# ICS.net
KiCad netlist of a schematic drawn in Altium Designer
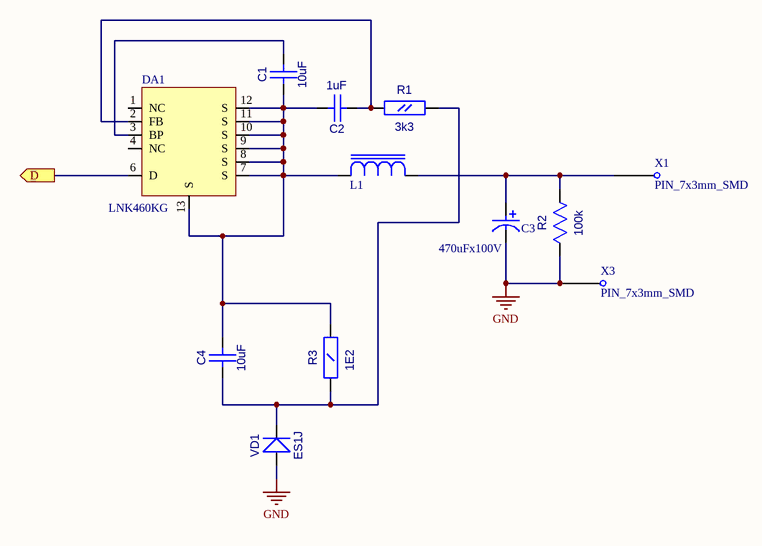
[diagram p0: ICS.SchDoc]

(export (version "E")
  (design (tool "Eeschema 10.0.6"))
  (components
    (comp (ref "C1")
      (value "10uF")
      (footprint "CC1206")
      (description "CC1206")
      (libsource (lib "gprs_modem_2") (part "CC1206"))
    )
    (comp (ref "C2")
      (value "1uF")
      (footprint "CC0805")
      (description "CC0805")
      (libsource (lib "gprs_modem_2") (part "CC0805"))
    )
    (comp (ref "C3")
      (value "470uFx100V")
      (footprint "CAP_7.5_SMD_2")
      (libsource (lib "gprs_modem_2") (part "CAP_16x25"))
    )
    (comp (ref "C4")
      (value "10uF")
      (footprint "CC1206")
      (description "CC1206")
      (libsource (lib "gprs_modem_2") (part "CC1206"))
    )
    (comp (ref "DA1")
      (value "LNK460KG")
      (footprint "eSOP-12")
      (libsource (lib "gprs_modem") (part "LNK460KG"))
    )
    (comp (ref "L1")
      (value "CDRH129HF-331MC")
      (footprint "IND_CDRH129")
      (libsource (lib "gprs_modem_2") (part "CDRH129"))
    )
    (comp (ref "R1")
      (value "3k3")
      (footprint "RC0805")
      (description "RC0805")
      (libsource (lib "gprs_modem_2") (part "RC0805"))
    )
    (comp (ref "R2")
      (value "100k")
      (footprint "RC0805")
      (description "RC0805")
      (libsource (lib "shlagbaum") (part "RC0805"))
    )
    (comp (ref "R3")
      (value "1E2")
      (footprint "RC1206")
      (description "RC1206")
      (libsource (lib "gprs_modem_2") (part "RC1206"))
    )
    (comp (ref "VD1")
      (value "ES1J")
      (footprint "SMA")
      (description "Schottky Rectifier")
      (libsource (lib "gprs_modem") (part "SS14"))
    )
    (comp (ref "X1")
      (value "PIN_7x3mm_SMD")
      (footprint "PIN_7x3mm_SMD")
      (libsource (lib "gprs_modem") (part "PIN_7x3mm_SMD"))
    )
    (comp (ref "X3")
      (value "PIN_7x3mm_SMD")
      (footprint "PIN_7x3mm_SMD")
      (libsource (lib "gprs_modem") (part "PIN_7x3mm_SMD"))
    )
  )
  (nets
    (net (code "1") (name "/D") (class "Default")
      (node (ref "DA1") (pin "6") (pinfunction "D_6") (pintype "passive"))
    )
    (net (code "2") (name "GND") (class "Default")
      (node (ref "C3") (pin "1") (pintype "passive"))
      (node (ref "R2") (pin "1") (pinfunction "A_1") (pintype "passive"))
      (node (ref "VD1") (pin "1") (pinfunction "A_1") (pintype "passive"))
      (node (ref "X3") (pin "1") (pinfunction "1_1") (pintype "passive"))
    )
    (net (code "3") (name "Net-(C1-A)") (class "Default")
      (node (ref "C1") (pin "1") (pinfunction "A_1") (pintype "passive"))
      (node (ref "C2") (pin "2") (pinfunction "B_2") (pintype "passive"))
      (node (ref "C4") (pin "2") (pinfunction "B_2") (pintype "passive"))
      (node (ref "DA1") (pin "10") (pinfunction "S_10") (pintype "passive"))
      (node (ref "DA1") (pin "11") (pinfunction "S_11") (pintype "passive"))
      (node (ref "DA1") (pin "12") (pinfunction "S_12") (pintype "passive"))
      (node (ref "DA1") (pin "13") (pinfunction "S_13") (pintype "passive"))
      (node (ref "DA1") (pin "7") (pinfunction "S_7") (pintype "passive"))
      (node (ref "DA1") (pin "8") (pinfunction "S_8") (pintype "passive"))
      (node (ref "DA1") (pin "9") (pinfunction "S_9") (pintype "passive"))
      (node (ref "L1") (pin "1") (pinfunction "A_1") (pintype "passive"))
      (node (ref "R3") (pin "2") (pinfunction "B_2") (pintype "passive"))
    )
    (net (code "4") (name "Net-(C1-B)") (class "Default")
      (node (ref "C1") (pin "2") (pinfunction "B_2") (pintype "passive"))
      (node (ref "DA1") (pin "3") (pinfunction "BP_3") (pintype "passive"))
    )
    (net (code "5") (name "Net-(C2-A)") (class "Default")
      (node (ref "C2") (pin "1") (pinfunction "A_1") (pintype "passive"))
      (node (ref "DA1") (pin "2") (pinfunction "FB_2") (pintype "passive"))
      (node (ref "R1") (pin "1") (pinfunction "A_1") (pintype "passive"))
    )
    (net (code "6") (name "Net-(C4-A)") (class "Default")
      (node (ref "C4") (pin "1") (pinfunction "A_1") (pintype "passive"))
      (node (ref "R1") (pin "2") (pinfunction "B_2") (pintype "passive"))
      (node (ref "R3") (pin "1") (pinfunction "A_1") (pintype "passive"))
      (node (ref "VD1") (pin "2") (pinfunction "K_2") (pintype "passive"))
    )
    (net (code "7") (name "Net-(L1-B)") (class "Default")
      (node (ref "C3") (pin "2") (pintype "passive"))
      (node (ref "L1") (pin "2") (pinfunction "B_2") (pintype "passive"))
      (node (ref "R2") (pin "2") (pinfunction "B_2") (pintype "passive"))
      (node (ref "X1") (pin "1") (pinfunction "1_1") (pintype "passive"))
    )
    (net (code "8") (name "unconnected-(DA1-NC-Pad1)") (class "Default")
      (node (ref "DA1") (pin "1") (pinfunction "NC_1") (pintype "passive"))
    )
    (net (code "9") (name "unconnected-(DA1-NC-Pad4)") (class "Default")
      (node (ref "DA1") (pin "4") (pinfunction "NC_4") (pintype "passive"))
    )
  )
)
